# GPSBee_v2.net
KiCad netlist of a schematic drawn in EAGLE
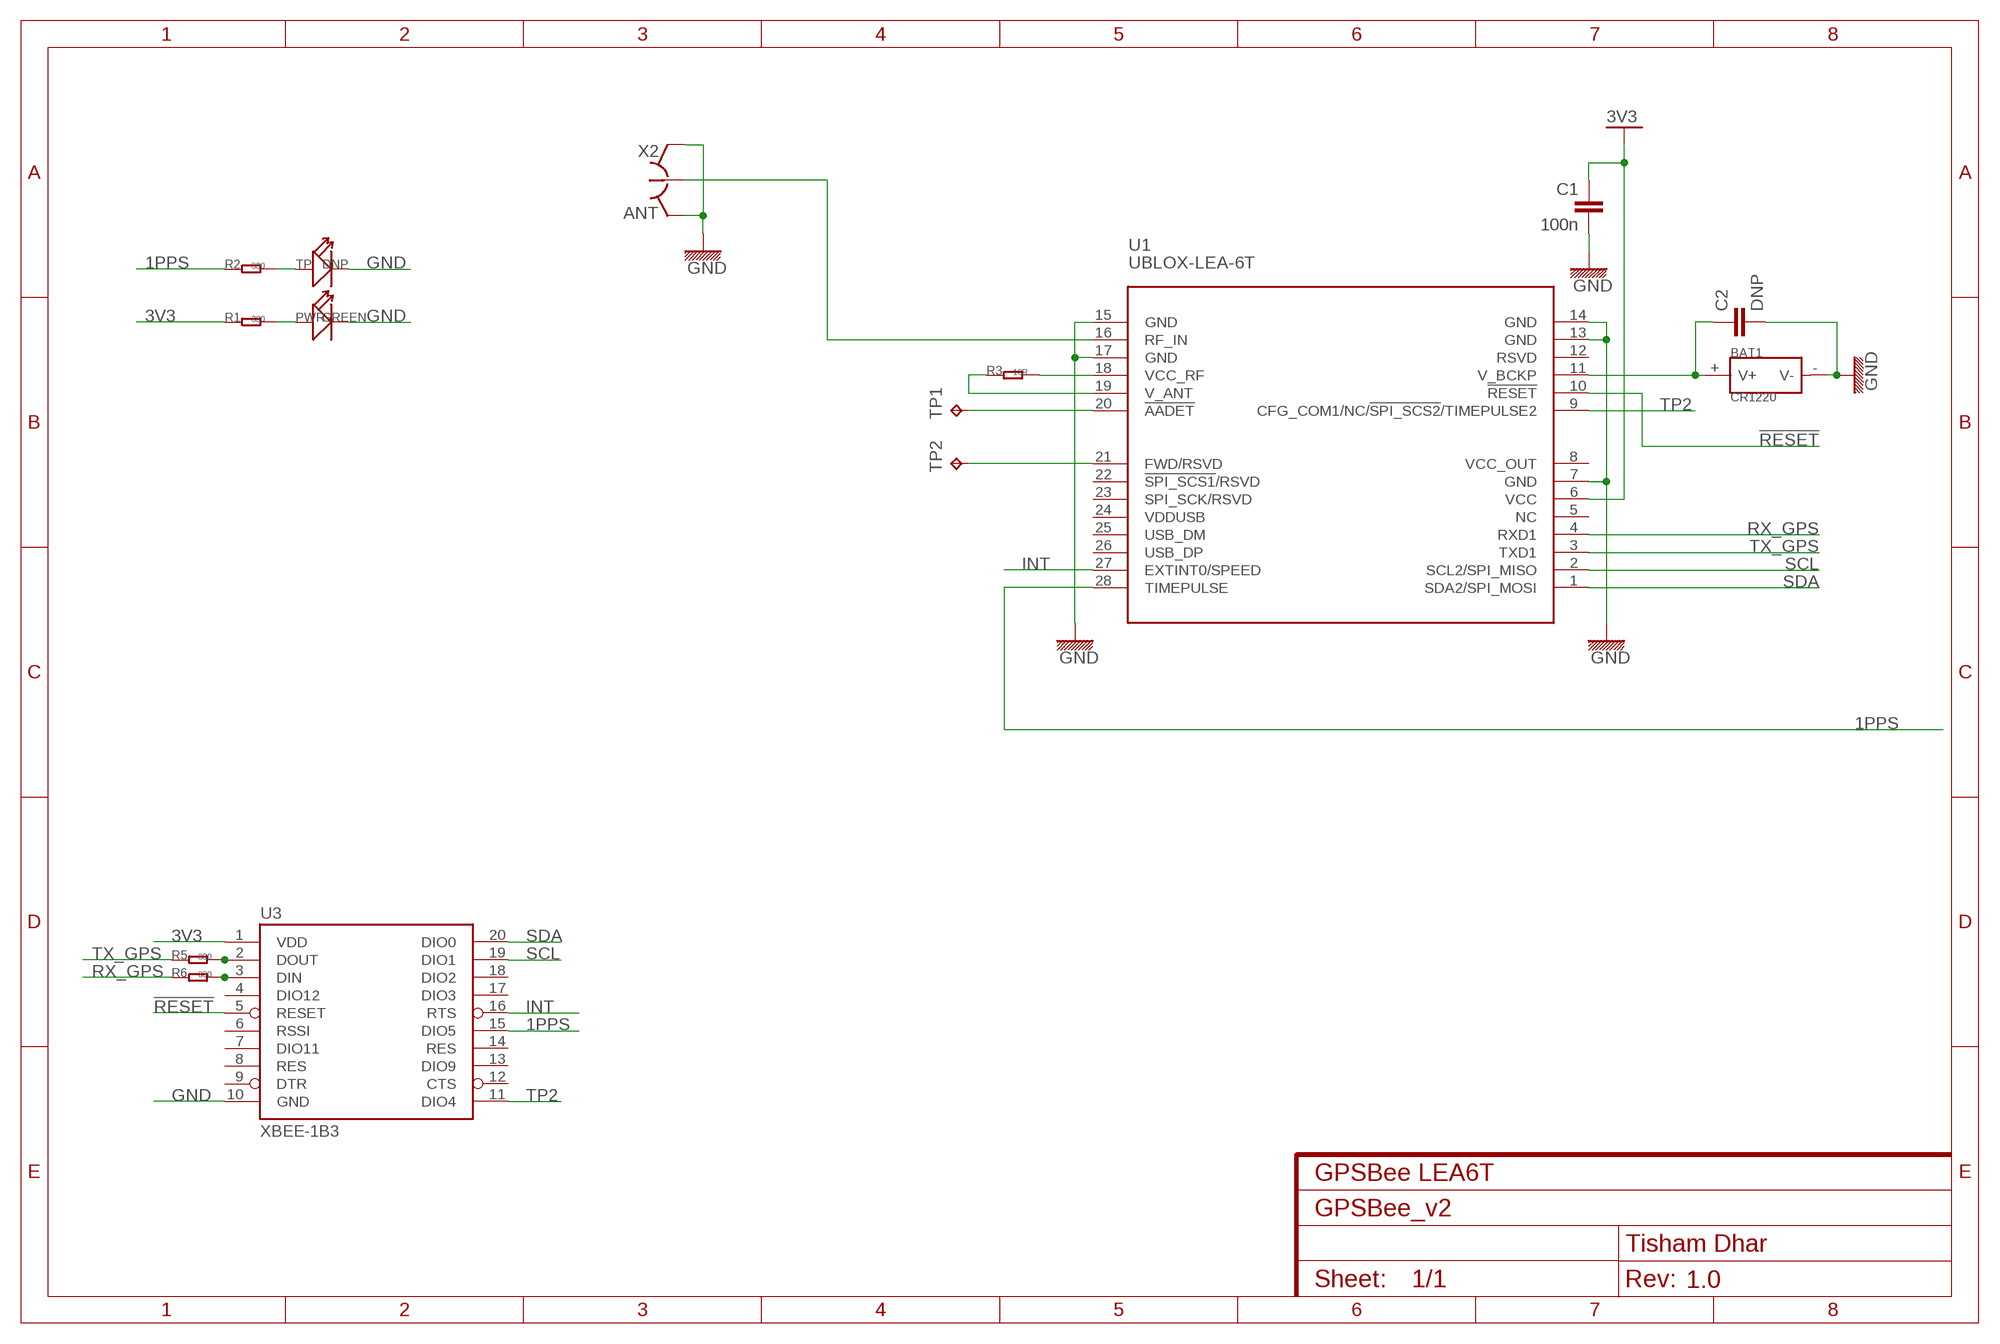
[diagram p0: schematic, sheet 1]

(export (version "E")
  (design (tool "Eeschema 10.0.6"))
  (components
    (comp (ref "BAT1")
      (value "CR1220")
      (footprint "eagle-import:PLASTIC-CR1220-L15.06XW13.0XH4.1MM")
      (libsource (lib "eagle-import") (part "BAT-HOLDER-SMD-1220"))
    )
    (comp (ref "C1")
      (value "100n")
      (footprint "eagle-import:0603")
      (libsource (lib "eagle-import") (part "C-EU_0603"))
    )
    (comp (ref "C2")
      (value "DNP")
      (footprint "eagle-import:0603")
      (libsource (lib "eagle-import") (part "C-EU_0603"))
    )
    (comp (ref "PWR")
      (value "GREEN")
      (footprint "eagle-import:LED-0603")
      (libsource (lib "eagle-import") (part "LED'0603'"))
    )
    (comp (ref "R1")
      (value "330")
      (footprint "eagle-import:0603")
      (libsource (lib "eagle-import") (part "R-0603"))
    )
    (comp (ref "R2")
      (value "330")
      (footprint "eagle-import:0603")
      (libsource (lib "eagle-import") (part "R-0603"))
    )
    (comp (ref "R3")
      (value "10R")
      (footprint "eagle-import:0603")
      (libsource (lib "eagle-import") (part "R-0603"))
    )
    (comp (ref "R5")
      (value "330")
      (footprint "eagle-import:0603")
      (libsource (lib "eagle-import") (part "R-0603"))
    )
    (comp (ref "R6")
      (value "330")
      (footprint "eagle-import:0603")
      (libsource (lib "eagle-import") (part "R-0603"))
    )
    (comp (ref "TP")
      (value "DNP")
      (footprint "eagle-import:LED-0603")
      (libsource (lib "eagle-import") (part "LED'0603'"))
    )
    (comp (ref "TP1")
      (value "TPTP10R")
      (footprint "eagle-import:TP10R")
      (libsource (lib "eagle-import") (part "TPTP10R"))
    )
    (comp (ref "TP2")
      (value "TPTP10R")
      (footprint "eagle-import:TP10R")
      (libsource (lib "eagle-import") (part "TPTP10R"))
    )
    (comp (ref "U1")
      (value "UBLOX-LEA-6T")
      (footprint "eagle-import:UBLOX-LEA-6")
      (libsource (lib "eagle-import") (part "UBLOX-LEA-6T"))
    )
    (comp (ref "U3")
      (value "XBEE-1B3")
      (footprint "eagle-import:XBEE-SMD")
      (libsource (lib "eagle-import") (part "XBEE-1B3"))
    )
    (comp (ref "X2")
      (value "ANT")
      (footprint "eagle-import:HRS_UFL")
      (libsource (lib "eagle-import") (part "HRS_UFL"))
    )
  )
  (nets
    (net (code "1") (name "/1PPS") (class "Default")
      (node (ref "R2") (pin "1") (pinfunction "1_1") (pintype "passive"))
      (node (ref "U1") (pin "28") (pinfunction "TIMEPULSE_28") (pintype "output"))
      (node (ref "U3") (pin "15") (pinfunction "DIO5_15") (pintype "bidirectional"))
    )
    (net (code "2") (name "/INT") (class "Default")
      (node (ref "U1") (pin "27") (pinfunction "EXTINT0/SPEED_27") (pintype "input"))
      (node (ref "U3") (pin "16") (pinfunction "RTS_16") (pintype "input"))
    )
    (net (code "3") (name "/RX_GPS") (class "Default")
      (node (ref "R6") (pin "1") (pinfunction "1_1") (pintype "passive"))
      (node (ref "U1") (pin "4") (pinfunction "RXD1_4") (pintype "input"))
    )
    (net (code "4") (name "/SCL") (class "Default")
      (node (ref "U1") (pin "2") (pinfunction "SCL2/SPI_MISO_2") (pintype "bidirectional"))
      (node (ref "U3") (pin "19") (pinfunction "DIO1_19") (pintype "bidirectional"))
    )
    (net (code "5") (name "/SDA") (class "Default")
      (node (ref "U1") (pin "1") (pinfunction "SDA2/SPI_MOSI_1") (pintype "bidirectional"))
      (node (ref "U3") (pin "20") (pinfunction "DIO0_20") (pintype "bidirectional"))
    )
    (net (code "6") (name "/TP2") (class "Default")
      (node (ref "U1") (pin "9") (pinfunction "CFG_COM1/NC/~{SPI_SCS2}/TIMEPULSE2_9") (pintype "bidirectional"))
      (node (ref "U3") (pin "11") (pinfunction "DIO4_11") (pintype "bidirectional"))
    )
    (net (code "7") (name "/TX_GPS") (class "Default")
      (node (ref "R5") (pin "1") (pinfunction "1_1") (pintype "passive"))
      (node (ref "U1") (pin "3") (pinfunction "TXD1_3") (pintype "output"))
    )
    (net (code "8") (name "/VCC_OUT") (class "Default")
      (node (ref "U1") (pin "8") (pinfunction "VCC_OUT_8") (pintype "power_in"))
    )
    (net (code "9") (name "/VDDUSB") (class "Default")
      (node (ref "U1") (pin "24") (pinfunction "VDDUSB_24") (pintype "power_in"))
    )
    (net (code "10") (name "/~{RESET}") (class "Default")
      (node (ref "U1") (pin "10") (pinfunction "~{RESET}_10") (pintype "input"))
      (node (ref "U3") (pin "5") (pinfunction "RESET_5") (pintype "input"))
    )
    (net (code "11") (name "3V3") (class "Default")
      (node (ref "C1") (pin "1") (pinfunction "1_1") (pintype "passive"))
      (node (ref "R1") (pin "1") (pinfunction "1_1") (pintype "passive"))
      (node (ref "U1") (pin "6") (pinfunction "VCC_6") (pintype "power_in"))
      (node (ref "U3") (pin "1") (pinfunction "VDD_1") (pintype "power_in"))
    )
    (net (code "12") (name "GND") (class "Default")
      (node (ref "BAT1") (pin "-") (pinfunction "V-_-") (pintype "bidirectional"))
      (node (ref "C1") (pin "2") (pinfunction "2_2") (pintype "passive"))
      (node (ref "C2") (pin "2") (pinfunction "2_2") (pintype "passive"))
      (node (ref "PWR") (pin "-") (pinfunction "-_-") (pintype "passive"))
      (node (ref "TP") (pin "-") (pinfunction "-_-") (pintype "passive"))
      (node (ref "U1") (pin "13") (pinfunction "GND_13") (pintype "power_in"))
      (node (ref "U1") (pin "14") (pinfunction "GND_14") (pintype "power_in"))
      (node (ref "U1") (pin "15") (pinfunction "GND_15") (pintype "power_in"))
      (node (ref "U1") (pin "17") (pinfunction "GND_17") (pintype "power_in"))
      (node (ref "U1") (pin "7") (pinfunction "GND_7") (pintype "power_in"))
      (node (ref "U3") (pin "10") (pinfunction "GND_10") (pintype "power_in"))
      (node (ref "X2") (pin "GND@1") (pinfunction "GND_GND@1") (pintype "power_in"))
      (node (ref "X2") (pin "GND@2") (pinfunction "GND_GND@2") (pintype "power_in"))
    )
    (net (code "13") (name "Net-(BAT1-V+)") (class "Default")
      (node (ref "BAT1") (pin "+") (pinfunction "V+_+") (pintype "bidirectional"))
      (node (ref "C2") (pin "1") (pinfunction "1_1") (pintype "passive"))
      (node (ref "U1") (pin "11") (pinfunction "V_BCKP_11") (pintype "power_in"))
    )
    (net (code "14") (name "Net-(PWR-Pad+)") (class "Default")
      (node (ref "PWR") (pin "+") (pinfunction "+_+") (pintype "passive"))
      (node (ref "R1") (pin "2") (pinfunction "2_2") (pintype "passive"))
    )
    (net (code "15") (name "Net-(R2-Pad2)") (class "Default")
      (node (ref "R2") (pin "2") (pinfunction "2_2") (pintype "passive"))
      (node (ref "TP") (pin "+") (pinfunction "+_+") (pintype "passive"))
    )
    (net (code "16") (name "Net-(U1-FWD{slash}RSVD)") (class "Default")
      (node (ref "TP2") (pin "TP") (pinfunction "TP_TP") (pintype "input"))
      (node (ref "U1") (pin "21") (pinfunction "FWD/RSVD_21") (pintype "input"))
    )
    (net (code "17") (name "Net-(U1-RF_IN)") (class "Default")
      (node (ref "U1") (pin "16") (pinfunction "RF_IN_16") (pintype "input"))
      (node (ref "X2") (pin "SIG") (pinfunction "1_SIG") (pintype "passive"))
    )
    (net (code "18") (name "Net-(U1-VCC_RF)") (class "Default")
      (node (ref "R3") (pin "2") (pinfunction "2_2") (pintype "passive"))
      (node (ref "U1") (pin "18") (pinfunction "VCC_RF_18") (pintype "power_in"))
    )
    (net (code "19") (name "Net-(U1-V_ANT)") (class "Default")
      (node (ref "R3") (pin "1") (pinfunction "1_1") (pintype "passive"))
      (node (ref "U1") (pin "19") (pinfunction "V_ANT_19") (pintype "power_in"))
    )
    (net (code "20") (name "Net-(U1-~{AADET})") (class "Default")
      (node (ref "TP1") (pin "TP") (pinfunction "TP_TP") (pintype "input"))
      (node (ref "U1") (pin "20") (pinfunction "~{AADET}_20") (pintype "input"))
    )
    (net (code "21") (name "Net-(U3-DIN)") (class "Default")
      (node (ref "R6") (pin "2") (pinfunction "2_2") (pintype "passive"))
      (node (ref "U3") (pin "3") (pinfunction "DIN_3") (pintype "input"))
    )
    (net (code "22") (name "Net-(U3-DOUT)") (class "Default")
      (node (ref "R5") (pin "2") (pinfunction "2_2") (pintype "passive"))
      (node (ref "U3") (pin "2") (pinfunction "DOUT_2") (pintype "output"))
    )
    (net (code "23") (name "unconnected-(U1-NC-Pad5)") (class "Default")
      (node (ref "U1") (pin "5") (pinfunction "NC_5") (pintype "no_connect"))
    )
    (net (code "24") (name "unconnected-(U1-RSVD-Pad12)") (class "Default")
      (node (ref "U1") (pin "12") (pinfunction "RSVD_12") (pintype "no_connect"))
    )
    (net (code "25") (name "unconnected-(U1-SPI_SCK{slash}RSVD-Pad23)") (class "Default")
      (node (ref "U1") (pin "23") (pinfunction "SPI_SCK/RSVD_23") (pintype "output"))
    )
    (net (code "26") (name "unconnected-(U1-USB_DM-Pad25)") (class "Default")
      (node (ref "U1") (pin "25") (pinfunction "USB_DM_25") (pintype "bidirectional"))
    )
    (net (code "27") (name "unconnected-(U1-USB_DP-Pad26)") (class "Default")
      (node (ref "U1") (pin "26") (pinfunction "USB_DP_26") (pintype "bidirectional"))
    )
    (net (code "28") (name "unconnected-(U1-~{SPI_SCS1}{slash}RSVD-Pad22)") (class "Default")
      (node (ref "U1") (pin "22") (pinfunction "~{SPI_SCS1}/RSVD_22") (pintype "output"))
    )
    (net (code "29") (name "unconnected-(U3-CTS-Pad12)") (class "Default")
      (node (ref "U3") (pin "12") (pinfunction "CTS_12") (pintype "output"))
    )
    (net (code "30") (name "unconnected-(U3-DIO2-Pad18)") (class "Default")
      (node (ref "U3") (pin "18") (pinfunction "DIO2_18") (pintype "bidirectional"))
    )
    (net (code "31") (name "unconnected-(U3-DIO3-Pad17)") (class "Default")
      (node (ref "U3") (pin "17") (pinfunction "DIO3_17") (pintype "bidirectional"))
    )
    (net (code "32") (name "unconnected-(U3-DIO9-Pad13)") (class "Default")
      (node (ref "U3") (pin "13") (pinfunction "DIO9_13") (pintype "bidirectional"))
    )
    (net (code "33") (name "unconnected-(U3-DIO11-Pad7)") (class "Default")
      (node (ref "U3") (pin "7") (pinfunction "DIO11_7") (pintype "bidirectional"))
    )
    (net (code "34") (name "unconnected-(U3-DIO12-Pad4)") (class "Default")
      (node (ref "U3") (pin "4") (pinfunction "DIO12_4") (pintype "bidirectional"))
    )
    (net (code "35") (name "unconnected-(U3-DTR-Pad9)") (class "Default")
      (node (ref "U3") (pin "9") (pinfunction "DTR_9") (pintype "bidirectional"))
    )
    (net (code "36") (name "unconnected-(U3-RES-Pad8)") (class "Default")
      (node (ref "U3") (pin "8") (pinfunction "RES_8") (pintype "bidirectional"))
    )
    (net (code "37") (name "unconnected-(U3-RES-Pad14)") (class "Default")
      (node (ref "U3") (pin "14") (pinfunction "RES_14") (pintype "bidirectional"))
    )
    (net (code "38") (name "unconnected-(U3-RSSI-Pad6)") (class "Default")
      (node (ref "U3") (pin "6") (pinfunction "RSSI_6") (pintype "bidirectional"))
    )
  )
)
